# Sheet3.net
KiCad netlist of a schematic drawn in Altium Designer
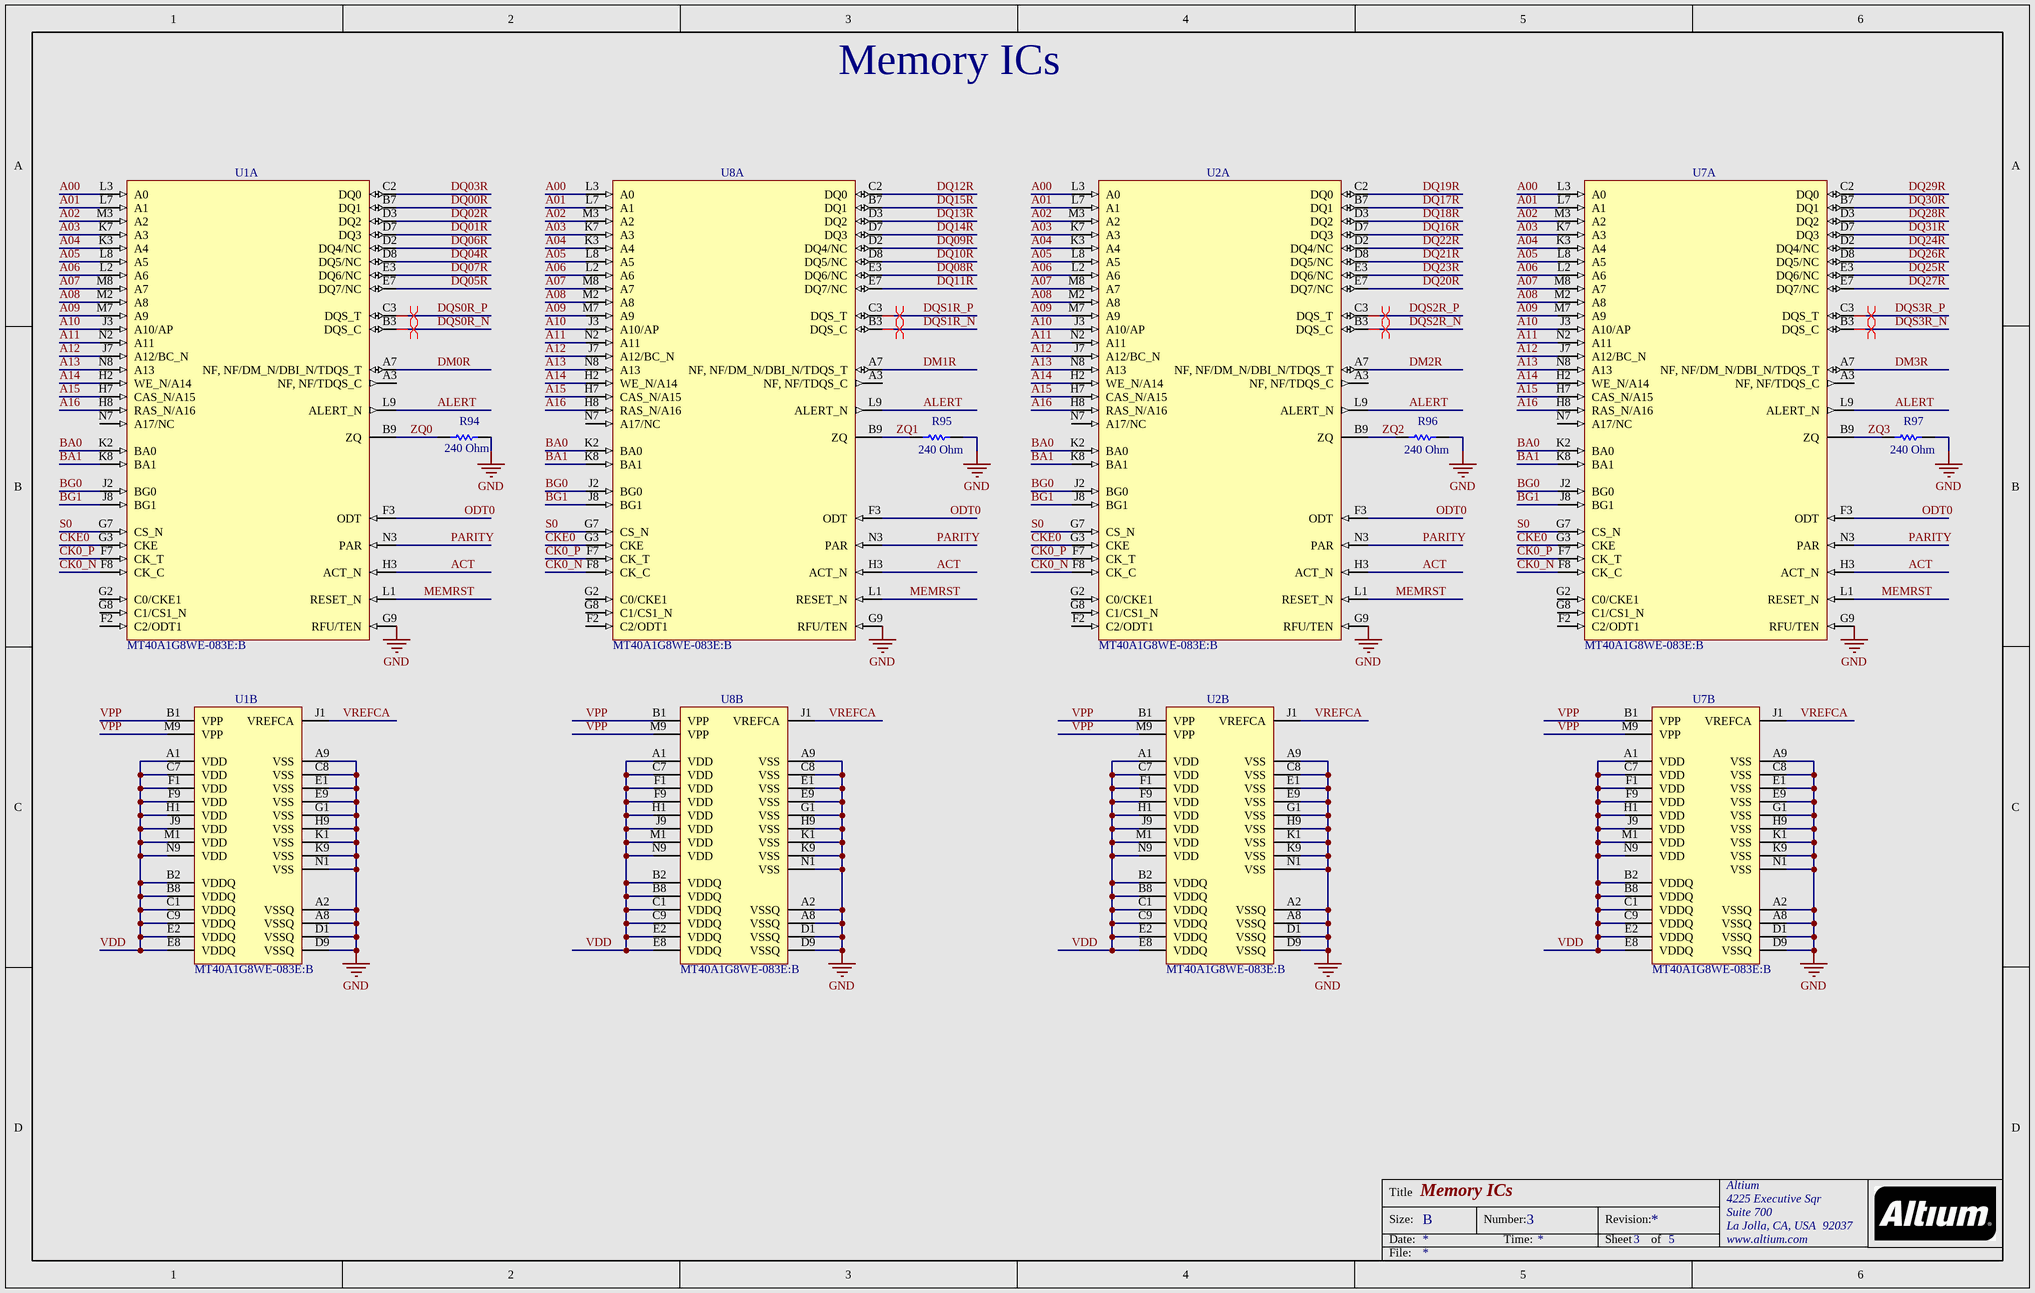
[diagram p0: Sheet3.SchDoc]

(export (version "E")
  (design (tool "Eeschema 10.0.6"))
  (components
    (comp (ref "R94")
      (value "ERJ-2GEJ241x")
      (footprint "RESC1005X40X25ML05T05")
      (description "Chip Resistor, 240 Ohm, +/- 5%, 100 mW, -55 to 155 degC, 0402 (1005 Metric), RoHS, Tape and Reel")
      (fields
        (field (name "RESISTANCE") "240 Ohm")
        (field (name "TOLERANCE") "5%")
        (field (name "MANUFACTURER") "Basic Passives")
      )
      (libsource (lib "Altium Content Vault") (part "CMP-2002-00493-3"))
    )
    (comp (ref "R95")
      (value "ERJ-2GEJ241x")
      (footprint "RESC1005X40X25ML05T05")
      (description "Chip Resistor, 240 Ohm, +/- 5%, 100 mW, -55 to 155 degC, 0402 (1005 Metric), RoHS, Tape and Reel")
      (fields
        (field (name "RESISTANCE") "240 Ohm")
        (field (name "TOLERANCE") "5%")
        (field (name "MANUFACTURER") "Basic Passives")
      )
      (libsource (lib "Altium Content Vault") (part "CMP-2002-00493-3"))
    )
    (comp (ref "R96")
      (value "ERJ-2GEJ241x")
      (footprint "RESC1005X40X25ML05T05")
      (description "Chip Resistor, 240 Ohm, +/- 5%, 100 mW, -55 to 155 degC, 0402 (1005 Metric), RoHS, Tape and Reel")
      (fields
        (field (name "RESISTANCE") "240 Ohm")
        (field (name "TOLERANCE") "5%")
        (field (name "MANUFACTURER") "Basic Passives")
      )
      (libsource (lib "Altium Content Vault") (part "CMP-2002-00493-3"))
    )
    (comp (ref "R97")
      (value "ERJ-2GEJ241x")
      (footprint "RESC1005X40X25ML05T05")
      (description "Chip Resistor, 240 Ohm, +/- 5%, 100 mW, -55 to 155 degC, 0402 (1005 Metric), RoHS, Tape and Reel")
      (fields
        (field (name "RESISTANCE") "240 Ohm")
        (field (name "TOLERANCE") "5%")
        (field (name "MANUFACTURER") "Basic Passives")
      )
      (libsource (lib "Altium Content Vault") (part "CMP-2002-00493-3"))
    )
    (comp (ref "U1")
      (value "MT40A1G8WE-083E:B")
      (footprint "MICT-WE-78")
      (description "8 Gb DDR4 SDRAM, 1 Gig x 8, 1.2 V, 0 to 95 degC, 78-Ball FBGA (WE), RoHS")
      (libsource (lib "Altium Content Vault") (part "CMP-1738-00001-1"))
    )
    (comp (ref "U2")
      (value "MT40A1G8WE-083E:B")
      (footprint "MICT-WE-78")
      (description "8 Gb DDR4 SDRAM, 1 Gig x 8, 1.2 V, 0 to 95 degC, 78-Ball FBGA (WE), RoHS")
      (libsource (lib "Altium Content Vault") (part "CMP-1738-00001-1"))
    )
    (comp (ref "U7")
      (value "MT40A1G8WE-083E:B")
      (footprint "MICT-WE-78")
      (description "8 Gb DDR4 SDRAM, 1 Gig x 8, 1.2 V, 0 to 95 degC, 78-Ball FBGA (WE), RoHS")
      (libsource (lib "Altium Content Vault") (part "CMP-1738-00001-1"))
    )
    (comp (ref "U8")
      (value "MT40A1G8WE-083E:B")
      (footprint "MICT-WE-78")
      (description "8 Gb DDR4 SDRAM, 1 Gig x 8, 1.2 V, 0 to 95 degC, 78-Ball FBGA (WE), RoHS")
      (libsource (lib "Altium Content Vault") (part "CMP-1738-00001-1"))
    )
  )
  (nets
    (net (code "1") (name "/A00") (class "Default")
      (node (ref "U1") (pin "L3") (pinfunction "A0_L3") (pintype "input"))
      (node (ref "U2") (pin "L3") (pinfunction "A0_L3") (pintype "input"))
      (node (ref "U7") (pin "L3") (pinfunction "A0_L3") (pintype "input"))
      (node (ref "U8") (pin "L3") (pinfunction "A0_L3") (pintype "input"))
    )
    (net (code "2") (name "/A01") (class "Default")
      (node (ref "U1") (pin "L7") (pinfunction "A1_L7") (pintype "input"))
      (node (ref "U2") (pin "L7") (pinfunction "A1_L7") (pintype "input"))
      (node (ref "U7") (pin "L7") (pinfunction "A1_L7") (pintype "input"))
      (node (ref "U8") (pin "L7") (pinfunction "A1_L7") (pintype "input"))
    )
    (net (code "3") (name "/A02") (class "Default")
      (node (ref "U1") (pin "M3") (pinfunction "A2_M3") (pintype "input"))
      (node (ref "U2") (pin "M3") (pinfunction "A2_M3") (pintype "input"))
      (node (ref "U7") (pin "M3") (pinfunction "A2_M3") (pintype "input"))
      (node (ref "U8") (pin "M3") (pinfunction "A2_M3") (pintype "input"))
    )
    (net (code "4") (name "/A03") (class "Default")
      (node (ref "U1") (pin "K7") (pinfunction "A3_K7") (pintype "input"))
      (node (ref "U2") (pin "K7") (pinfunction "A3_K7") (pintype "input"))
      (node (ref "U7") (pin "K7") (pinfunction "A3_K7") (pintype "input"))
      (node (ref "U8") (pin "K7") (pinfunction "A3_K7") (pintype "input"))
    )
    (net (code "5") (name "/A04") (class "Default")
      (node (ref "U1") (pin "K3") (pinfunction "A4_K3") (pintype "input"))
      (node (ref "U2") (pin "K3") (pinfunction "A4_K3") (pintype "input"))
      (node (ref "U7") (pin "K3") (pinfunction "A4_K3") (pintype "input"))
      (node (ref "U8") (pin "K3") (pinfunction "A4_K3") (pintype "input"))
    )
    (net (code "6") (name "/A05") (class "Default")
      (node (ref "U1") (pin "L8") (pinfunction "A5_L8") (pintype "input"))
      (node (ref "U2") (pin "L8") (pinfunction "A5_L8") (pintype "input"))
      (node (ref "U7") (pin "L8") (pinfunction "A5_L8") (pintype "input"))
      (node (ref "U8") (pin "L8") (pinfunction "A5_L8") (pintype "input"))
    )
    (net (code "7") (name "/A06") (class "Default")
      (node (ref "U1") (pin "L2") (pinfunction "A6_L2") (pintype "input"))
      (node (ref "U2") (pin "L2") (pinfunction "A6_L2") (pintype "input"))
      (node (ref "U7") (pin "L2") (pinfunction "A6_L2") (pintype "input"))
      (node (ref "U8") (pin "L2") (pinfunction "A6_L2") (pintype "input"))
    )
    (net (code "8") (name "/A07") (class "Default")
      (node (ref "U1") (pin "M8") (pinfunction "A7_M8") (pintype "input"))
      (node (ref "U2") (pin "M8") (pinfunction "A7_M8") (pintype "input"))
      (node (ref "U7") (pin "M8") (pinfunction "A7_M8") (pintype "input"))
      (node (ref "U8") (pin "M8") (pinfunction "A7_M8") (pintype "input"))
    )
    (net (code "9") (name "/A08") (class "Default")
      (node (ref "U1") (pin "M2") (pinfunction "A8_M2") (pintype "input"))
      (node (ref "U2") (pin "M2") (pinfunction "A8_M2") (pintype "input"))
      (node (ref "U7") (pin "M2") (pinfunction "A8_M2") (pintype "input"))
      (node (ref "U8") (pin "M2") (pinfunction "A8_M2") (pintype "input"))
    )
    (net (code "10") (name "/A09") (class "Default")
      (node (ref "U1") (pin "M7") (pinfunction "A9_M7") (pintype "input"))
      (node (ref "U2") (pin "M7") (pinfunction "A9_M7") (pintype "input"))
      (node (ref "U7") (pin "M7") (pinfunction "A9_M7") (pintype "input"))
      (node (ref "U8") (pin "M7") (pinfunction "A9_M7") (pintype "input"))
    )
    (net (code "11") (name "/A10") (class "Default")
      (node (ref "U1") (pin "J3") (pinfunction "A10/AP_J3") (pintype "input"))
      (node (ref "U2") (pin "J3") (pinfunction "A10/AP_J3") (pintype "input"))
      (node (ref "U7") (pin "J3") (pinfunction "A10/AP_J3") (pintype "input"))
      (node (ref "U8") (pin "J3") (pinfunction "A10/AP_J3") (pintype "input"))
    )
    (net (code "12") (name "/A11") (class "Default")
      (node (ref "U1") (pin "N2") (pinfunction "A11_N2") (pintype "input"))
      (node (ref "U2") (pin "N2") (pinfunction "A11_N2") (pintype "input"))
      (node (ref "U7") (pin "N2") (pinfunction "A11_N2") (pintype "input"))
      (node (ref "U8") (pin "N2") (pinfunction "A11_N2") (pintype "input"))
    )
    (net (code "13") (name "/A12") (class "Default")
      (node (ref "U1") (pin "J7") (pinfunction "A12/BC_N_J7") (pintype "input"))
      (node (ref "U2") (pin "J7") (pinfunction "A12/BC_N_J7") (pintype "input"))
      (node (ref "U7") (pin "J7") (pinfunction "A12/BC_N_J7") (pintype "input"))
      (node (ref "U8") (pin "J7") (pinfunction "A12/BC_N_J7") (pintype "input"))
    )
    (net (code "14") (name "/A13") (class "Default")
      (node (ref "U1") (pin "N8") (pinfunction "A13_N8") (pintype "input"))
      (node (ref "U2") (pin "N8") (pinfunction "A13_N8") (pintype "input"))
      (node (ref "U7") (pin "N8") (pinfunction "A13_N8") (pintype "input"))
      (node (ref "U8") (pin "N8") (pinfunction "A13_N8") (pintype "input"))
    )
    (net (code "15") (name "/A14") (class "Default")
      (node (ref "U1") (pin "H2") (pinfunction "WE_N/A14_H2") (pintype "input"))
      (node (ref "U2") (pin "H2") (pinfunction "WE_N/A14_H2") (pintype "input"))
      (node (ref "U7") (pin "H2") (pinfunction "WE_N/A14_H2") (pintype "input"))
      (node (ref "U8") (pin "H2") (pinfunction "WE_N/A14_H2") (pintype "input"))
    )
    (net (code "16") (name "/A15") (class "Default")
      (node (ref "U1") (pin "H7") (pinfunction "CAS_N/A15_H7") (pintype "input"))
      (node (ref "U2") (pin "H7") (pinfunction "CAS_N/A15_H7") (pintype "input"))
      (node (ref "U7") (pin "H7") (pinfunction "CAS_N/A15_H7") (pintype "input"))
      (node (ref "U8") (pin "H7") (pinfunction "CAS_N/A15_H7") (pintype "input"))
    )
    (net (code "17") (name "/A16") (class "Default")
      (node (ref "U1") (pin "H8") (pinfunction "RAS_N/A16_H8") (pintype "input"))
      (node (ref "U2") (pin "H8") (pinfunction "RAS_N/A16_H8") (pintype "input"))
      (node (ref "U7") (pin "H8") (pinfunction "RAS_N/A16_H8") (pintype "input"))
      (node (ref "U8") (pin "H8") (pinfunction "RAS_N/A16_H8") (pintype "input"))
    )
    (net (code "18") (name "/ACT") (class "Default")
      (node (ref "U1") (pin "H3") (pinfunction "ACT_N_H3") (pintype "input"))
      (node (ref "U2") (pin "H3") (pinfunction "ACT_N_H3") (pintype "input"))
      (node (ref "U7") (pin "H3") (pinfunction "ACT_N_H3") (pintype "input"))
      (node (ref "U8") (pin "H3") (pinfunction "ACT_N_H3") (pintype "input"))
    )
    (net (code "19") (name "/ALERT") (class "Default")
      (node (ref "U1") (pin "L9") (pinfunction "ALERT_N_L9") (pintype "output"))
      (node (ref "U2") (pin "L9") (pinfunction "ALERT_N_L9") (pintype "output"))
      (node (ref "U7") (pin "L9") (pinfunction "ALERT_N_L9") (pintype "output"))
      (node (ref "U8") (pin "L9") (pinfunction "ALERT_N_L9") (pintype "output"))
    )
    (net (code "20") (name "/BA0") (class "Default")
      (node (ref "U1") (pin "K2") (pinfunction "BA0_K2") (pintype "input"))
      (node (ref "U2") (pin "K2") (pinfunction "BA0_K2") (pintype "input"))
      (node (ref "U7") (pin "K2") (pinfunction "BA0_K2") (pintype "input"))
      (node (ref "U8") (pin "K2") (pinfunction "BA0_K2") (pintype "input"))
    )
    (net (code "21") (name "/BA1") (class "Default")
      (node (ref "U1") (pin "K8") (pinfunction "BA1_K8") (pintype "input"))
      (node (ref "U2") (pin "K8") (pinfunction "BA1_K8") (pintype "input"))
      (node (ref "U7") (pin "K8") (pinfunction "BA1_K8") (pintype "input"))
      (node (ref "U8") (pin "K8") (pinfunction "BA1_K8") (pintype "input"))
    )
    (net (code "22") (name "/BG0") (class "Default")
      (node (ref "U1") (pin "J2") (pinfunction "BG0_J2") (pintype "input"))
      (node (ref "U2") (pin "J2") (pinfunction "BG0_J2") (pintype "input"))
      (node (ref "U7") (pin "J2") (pinfunction "BG0_J2") (pintype "input"))
      (node (ref "U8") (pin "J2") (pinfunction "BG0_J2") (pintype "input"))
    )
    (net (code "23") (name "/BG1") (class "Default")
      (node (ref "U1") (pin "J8") (pinfunction "BG1_J8") (pintype "input"))
      (node (ref "U2") (pin "J8") (pinfunction "BG1_J8") (pintype "input"))
      (node (ref "U7") (pin "J8") (pinfunction "BG1_J8") (pintype "input"))
      (node (ref "U8") (pin "J8") (pinfunction "BG1_J8") (pintype "input"))
    )
    (net (code "24") (name "/CK0_N") (class "Default")
      (node (ref "U1") (pin "F8") (pinfunction "CK_C_F8") (pintype "input"))
      (node (ref "U2") (pin "F8") (pinfunction "CK_C_F8") (pintype "input"))
      (node (ref "U7") (pin "F8") (pinfunction "CK_C_F8") (pintype "input"))
      (node (ref "U8") (pin "F8") (pinfunction "CK_C_F8") (pintype "input"))
    )
    (net (code "25") (name "/CK0_P") (class "Default")
      (node (ref "U1") (pin "F7") (pinfunction "CK_T_F7") (pintype "input"))
      (node (ref "U2") (pin "F7") (pinfunction "CK_T_F7") (pintype "input"))
      (node (ref "U7") (pin "F7") (pinfunction "CK_T_F7") (pintype "input"))
      (node (ref "U8") (pin "F7") (pinfunction "CK_T_F7") (pintype "input"))
    )
    (net (code "26") (name "/CKE0") (class "Default")
      (node (ref "U1") (pin "G3") (pinfunction "CKE_G3") (pintype "input"))
      (node (ref "U2") (pin "G3") (pinfunction "CKE_G3") (pintype "input"))
      (node (ref "U7") (pin "G3") (pinfunction "CKE_G3") (pintype "input"))
      (node (ref "U8") (pin "G3") (pinfunction "CKE_G3") (pintype "input"))
    )
    (net (code "27") (name "/DM0R") (class "Default")
      (node (ref "U1") (pin "A7") (pinfunction "NF,_NF/DM_N/DBI_N/TDQS_T_A7") (pintype "bidirectional"))
    )
    (net (code "28") (name "/DM1R") (class "Default")
      (node (ref "U8") (pin "A7") (pinfunction "NF,_NF/DM_N/DBI_N/TDQS_T_A7") (pintype "bidirectional"))
    )
    (net (code "29") (name "/DM2R") (class "Default")
      (node (ref "U2") (pin "A7") (pinfunction "NF,_NF/DM_N/DBI_N/TDQS_T_A7") (pintype "bidirectional"))
    )
    (net (code "30") (name "/DM3R") (class "Default")
      (node (ref "U7") (pin "A7") (pinfunction "NF,_NF/DM_N/DBI_N/TDQS_T_A7") (pintype "bidirectional"))
    )
    (net (code "31") (name "/DQ00R") (class "Default")
      (node (ref "U1") (pin "B7") (pinfunction "DQ1_B7") (pintype "bidirectional"))
    )
    (net (code "32") (name "/DQ01R") (class "Default")
      (node (ref "U1") (pin "D7") (pinfunction "DQ3_D7") (pintype "bidirectional"))
    )
    (net (code "33") (name "/DQ02R") (class "Default")
      (node (ref "U1") (pin "D3") (pinfunction "DQ2_D3") (pintype "bidirectional"))
    )
    (net (code "34") (name "/DQ03R") (class "Default")
      (node (ref "U1") (pin "C2") (pinfunction "DQ0_C2") (pintype "bidirectional"))
    )
    (net (code "35") (name "/DQ04R") (class "Default")
      (node (ref "U1") (pin "D8") (pinfunction "DQ5/NC_D8") (pintype "bidirectional"))
    )
    (net (code "36") (name "/DQ05R") (class "Default")
      (node (ref "U1") (pin "E7") (pinfunction "DQ7/NC_E7") (pintype "bidirectional"))
    )
    (net (code "37") (name "/DQ06R") (class "Default")
      (node (ref "U1") (pin "D2") (pinfunction "DQ4/NC_D2") (pintype "bidirectional"))
    )
    (net (code "38") (name "/DQ07R") (class "Default")
      (node (ref "U1") (pin "E3") (pinfunction "DQ6/NC_E3") (pintype "bidirectional"))
    )
    (net (code "39") (name "/DQ08R") (class "Default")
      (node (ref "U8") (pin "E3") (pinfunction "DQ6/NC_E3") (pintype "bidirectional"))
    )
    (net (code "40") (name "/DQ09R") (class "Default")
      (node (ref "U8") (pin "D2") (pinfunction "DQ4/NC_D2") (pintype "bidirectional"))
    )
    (net (code "41") (name "/DQ10R") (class "Default")
      (node (ref "U8") (pin "D8") (pinfunction "DQ5/NC_D8") (pintype "bidirectional"))
    )
    (net (code "42") (name "/DQ11R") (class "Default")
      (node (ref "U8") (pin "E7") (pinfunction "DQ7/NC_E7") (pintype "bidirectional"))
    )
    (net (code "43") (name "/DQ12R") (class "Default")
      (node (ref "U8") (pin "C2") (pinfunction "DQ0_C2") (pintype "bidirectional"))
    )
    (net (code "44") (name "/DQ13R") (class "Default")
      (node (ref "U8") (pin "D3") (pinfunction "DQ2_D3") (pintype "bidirectional"))
    )
    (net (code "45") (name "/DQ14R") (class "Default")
      (node (ref "U8") (pin "D7") (pinfunction "DQ3_D7") (pintype "bidirectional"))
    )
    (net (code "46") (name "/DQ15R") (class "Default")
      (node (ref "U8") (pin "B7") (pinfunction "DQ1_B7") (pintype "bidirectional"))
    )
    (net (code "47") (name "/DQ16R") (class "Default")
      (node (ref "U2") (pin "D7") (pinfunction "DQ3_D7") (pintype "bidirectional"))
    )
    (net (code "48") (name "/DQ17R") (class "Default")
      (node (ref "U2") (pin "B7") (pinfunction "DQ1_B7") (pintype "bidirectional"))
    )
    (net (code "49") (name "/DQ18R") (class "Default")
      (node (ref "U2") (pin "D3") (pinfunction "DQ2_D3") (pintype "bidirectional"))
    )
    (net (code "50") (name "/DQ19R") (class "Default")
      (node (ref "U2") (pin "C2") (pinfunction "DQ0_C2") (pintype "bidirectional"))
    )
    (net (code "51") (name "/DQ20R") (class "Default")
      (node (ref "U2") (pin "E7") (pinfunction "DQ7/NC_E7") (pintype "bidirectional"))
    )
    (net (code "52") (name "/DQ21R") (class "Default")
      (node (ref "U2") (pin "D8") (pinfunction "DQ5/NC_D8") (pintype "bidirectional"))
    )
    (net (code "53") (name "/DQ22R") (class "Default")
      (node (ref "U2") (pin "D2") (pinfunction "DQ4/NC_D2") (pintype "bidirectional"))
    )
    (net (code "54") (name "/DQ23R") (class "Default")
      (node (ref "U2") (pin "E3") (pinfunction "DQ6/NC_E3") (pintype "bidirectional"))
    )
    (net (code "55") (name "/DQ24R") (class "Default")
      (node (ref "U7") (pin "D2") (pinfunction "DQ4/NC_D2") (pintype "bidirectional"))
    )
    (net (code "56") (name "/DQ25R") (class "Default")
      (node (ref "U7") (pin "E3") (pinfunction "DQ6/NC_E3") (pintype "bidirectional"))
    )
    (net (code "57") (name "/DQ26R") (class "Default")
      (node (ref "U7") (pin "D8") (pinfunction "DQ5/NC_D8") (pintype "bidirectional"))
    )
    (net (code "58") (name "/DQ27R") (class "Default")
      (node (ref "U7") (pin "E7") (pinfunction "DQ7/NC_E7") (pintype "bidirectional"))
    )
    (net (code "59") (name "/DQ28R") (class "Default")
      (node (ref "U7") (pin "D3") (pinfunction "DQ2_D3") (pintype "bidirectional"))
    )
    (net (code "60") (name "/DQ29R") (class "Default")
      (node (ref "U7") (pin "C2") (pinfunction "DQ0_C2") (pintype "bidirectional"))
    )
    (net (code "61") (name "/DQ30R") (class "Default")
      (node (ref "U7") (pin "B7") (pinfunction "DQ1_B7") (pintype "bidirectional"))
    )
    (net (code "62") (name "/DQ31R") (class "Default")
      (node (ref "U7") (pin "D7") (pinfunction "DQ3_D7") (pintype "bidirectional"))
    )
    (net (code "63") (name "/DQS0R_N") (class "Default")
      (node (ref "U1") (pin "B3") (pinfunction "DQS_C_B3") (pintype "bidirectional"))
    )
    (net (code "64") (name "/DQS0R_P") (class "Default")
      (node (ref "U1") (pin "C3") (pinfunction "DQS_T_C3") (pintype "bidirectional"))
    )
    (net (code "65") (name "/DQS1R_N") (class "Default")
      (node (ref "U8") (pin "B3") (pinfunction "DQS_C_B3") (pintype "bidirectional"))
    )
    (net (code "66") (name "/DQS1R_P") (class "Default")
      (node (ref "U8") (pin "C3") (pinfunction "DQS_T_C3") (pintype "bidirectional"))
    )
    (net (code "67") (name "/DQS2R_N") (class "Default")
      (node (ref "U2") (pin "B3") (pinfunction "DQS_C_B3") (pintype "bidirectional"))
    )
    (net (code "68") (name "/DQS2R_P") (class "Default")
      (node (ref "U2") (pin "C3") (pinfunction "DQS_T_C3") (pintype "bidirectional"))
    )
    (net (code "69") (name "/DQS3R_N") (class "Default")
      (node (ref "U7") (pin "B3") (pinfunction "DQS_C_B3") (pintype "bidirectional"))
    )
    (net (code "70") (name "/DQS3R_P") (class "Default")
      (node (ref "U7") (pin "C3") (pinfunction "DQS_T_C3") (pintype "bidirectional"))
    )
    (net (code "71") (name "/MEMRST") (class "Default")
      (node (ref "U1") (pin "L1") (pinfunction "RESET_N_L1") (pintype "input"))
      (node (ref "U2") (pin "L1") (pinfunction "RESET_N_L1") (pintype "input"))
      (node (ref "U7") (pin "L1") (pinfunction "RESET_N_L1") (pintype "input"))
      (node (ref "U8") (pin "L1") (pinfunction "RESET_N_L1") (pintype "input"))
    )
    (net (code "72") (name "/ODT0") (class "Default")
      (node (ref "U1") (pin "F3") (pinfunction "ODT_F3") (pintype "input"))
      (node (ref "U2") (pin "F3") (pinfunction "ODT_F3") (pintype "input"))
      (node (ref "U7") (pin "F3") (pinfunction "ODT_F3") (pintype "input"))
      (node (ref "U8") (pin "F3") (pinfunction "ODT_F3") (pintype "input"))
    )
    (net (code "73") (name "/PARITY") (class "Default")
      (node (ref "U1") (pin "N3") (pinfunction "PAR_N3") (pintype "input"))
      (node (ref "U2") (pin "N3") (pinfunction "PAR_N3") (pintype "input"))
      (node (ref "U7") (pin "N3") (pinfunction "PAR_N3") (pintype "input"))
      (node (ref "U8") (pin "N3") (pinfunction "PAR_N3") (pintype "input"))
    )
    (net (code "74") (name "/S0") (class "Default")
      (node (ref "U1") (pin "G7") (pinfunction "CS_N_G7") (pintype "input"))
      (node (ref "U2") (pin "G7") (pinfunction "CS_N_G7") (pintype "input"))
      (node (ref "U7") (pin "G7") (pinfunction "CS_N_G7") (pintype "input"))
      (node (ref "U8") (pin "G7") (pinfunction "CS_N_G7") (pintype "input"))
    )
    (net (code "75") (name "/VDD") (class "Default")
      (node (ref "U1") (pin "A1") (pinfunction "VDD_A1") (pintype "power_in"))
      (node (ref "U1") (pin "B2") (pinfunction "VDDQ_B2") (pintype "power_in"))
      (node (ref "U1") (pin "B8") (pinfunction "VDDQ_B8") (pintype "power_in"))
      (node (ref "U1") (pin "C1") (pinfunction "VDDQ_C1") (pintype "power_in"))
      (node (ref "U1") (pin "C7") (pinfunction "VDD_C7") (pintype "power_in"))
      (node (ref "U1") (pin "C9") (pinfunction "VDDQ_C9") (pintype "power_in"))
      (node (ref "U1") (pin "E2") (pinfunction "VDDQ_E2") (pintype "power_in"))
      (node (ref "U1") (pin "E8") (pinfunction "VDDQ_E8") (pintype "power_in"))
      (node (ref "U1") (pin "F1") (pinfunction "VDD_F1") (pintype "power_in"))
      (node (ref "U1") (pin "F9") (pinfunction "VDD_F9") (pintype "power_in"))
      (node (ref "U1") (pin "H1") (pinfunction "VDD_H1") (pintype "power_in"))
      (node (ref "U1") (pin "J9") (pinfunction "VDD_J9") (pintype "power_in"))
      (node (ref "U1") (pin "M1") (pinfunction "VDD_M1") (pintype "power_in"))
      (node (ref "U1") (pin "N9") (pinfunction "VDD_N9") (pintype "power_in"))
      (node (ref "U2") (pin "A1") (pinfunction "VDD_A1") (pintype "power_in"))
      (node (ref "U2") (pin "B2") (pinfunction "VDDQ_B2") (pintype "power_in"))
      (node (ref "U2") (pin "B8") (pinfunction "VDDQ_B8") (pintype "power_in"))
      (node (ref "U2") (pin "C1") (pinfunction "VDDQ_C1") (pintype "power_in"))
      (node (ref "U2") (pin "C7") (pinfunction "VDD_C7") (pintype "power_in"))
      (node (ref "U2") (pin "C9") (pinfunction "VDDQ_C9") (pintype "power_in"))
      (node (ref "U2") (pin "E2") (pinfunction "VDDQ_E2") (pintype "power_in"))
      (node (ref "U2") (pin "E8") (pinfunction "VDDQ_E8") (pintype "power_in"))
      (node (ref "U2") (pin "F1") (pinfunction "VDD_F1") (pintype "power_in"))
      (node (ref "U2") (pin "F9") (pinfunction "VDD_F9") (pintype "power_in"))
      (node (ref "U2") (pin "H1") (pinfunction "VDD_H1") (pintype "power_in"))
      (node (ref "U2") (pin "J9") (pinfunction "VDD_J9") (pintype "power_in"))
      (node (ref "U2") (pin "M1") (pinfunction "VDD_M1") (pintype "power_in"))
      (node (ref "U2") (pin "N9") (pinfunction "VDD_N9") (pintype "power_in"))
      (node (ref "U7") (pin "A1") (pinfunction "VDD_A1") (pintype "power_in"))
      (node (ref "U7") (pin "B2") (pinfunction "VDDQ_B2") (pintype "power_in"))
      (node (ref "U7") (pin "B8") (pinfunction "VDDQ_B8") (pintype "power_in"))
      (node (ref "U7") (pin "C1") (pinfunction "VDDQ_C1") (pintype "power_in"))
      (node (ref "U7") (pin "C7") (pinfunction "VDD_C7") (pintype "power_in"))
      (node (ref "U7") (pin "C9") (pinfunction "VDDQ_C9") (pintype "power_in"))
      (node (ref "U7") (pin "E2") (pinfunction "VDDQ_E2") (pintype "power_in"))
      (node (ref "U7") (pin "E8") (pinfunction "VDDQ_E8") (pintype "power_in"))
      (node (ref "U7") (pin "F1") (pinfunction "VDD_F1") (pintype "power_in"))
      (node (ref "U7") (pin "F9") (pinfunction "VDD_F9") (pintype "power_in"))
      (node (ref "U7") (pin "H1") (pinfunction "VDD_H1") (pintype "power_in"))
      (node (ref "U7") (pin "J9") (pinfunction "VDD_J9") (pintype "power_in"))
      (node (ref "U7") (pin "M1") (pinfunction "VDD_M1") (pintype "power_in"))
      (node (ref "U7") (pin "N9") (pinfunction "VDD_N9") (pintype "power_in"))
      (node (ref "U8") (pin "A1") (pinfunction "VDD_A1") (pintype "power_in"))
      (node (ref "U8") (pin "B2") (pinfunction "VDDQ_B2") (pintype "power_in"))
      (node (ref "U8") (pin "B8") (pinfunction "VDDQ_B8") (pintype "power_in"))
      (node (ref "U8") (pin "C1") (pinfunction "VDDQ_C1") (pintype "power_in"))
      (node (ref "U8") (pin "C7") (pinfunction "VDD_C7") (pintype "power_in"))
      (node (ref "U8") (pin "C9") (pinfunction "VDDQ_C9") (pintype "power_in"))
      (node (ref "U8") (pin "E2") (pinfunction "VDDQ_E2") (pintype "power_in"))
      (node (ref "U8") (pin "E8") (pinfunction "VDDQ_E8") (pintype "power_in"))
      (node (ref "U8") (pin "F1") (pinfunction "VDD_F1") (pintype "power_in"))
      (node (ref "U8") (pin "F9") (pinfunction "VDD_F9") (pintype "power_in"))
      (node (ref "U8") (pin "H1") (pinfunction "VDD_H1") (pintype "power_in"))
      (node (ref "U8") (pin "J9") (pinfunction "VDD_J9") (pintype "power_in"))
      (node (ref "U8") (pin "M1") (pinfunction "VDD_M1") (pintype "power_in"))
      (node (ref "U8") (pin "N9") (pinfunction "VDD_N9") (pintype "power_in"))
    )
    (net (code "76") (name "/VPP") (class "Default")
      (node (ref "U1") (pin "B1") (pinfunction "VPP_B1") (pintype "power_in"))
      (node (ref "U1") (pin "M9") (pinfunction "VPP_M9") (pintype "power_in"))
      (node (ref "U2") (pin "B1") (pinfunction "VPP_B1") (pintype "power_in"))
      (node (ref "U2") (pin "M9") (pinfunction "VPP_M9") (pintype "power_in"))
      (node (ref "U7") (pin "B1") (pinfunction "VPP_B1") (pintype "power_in"))
      (node (ref "U7") (pin "M9") (pinfunction "VPP_M9") (pintype "power_in"))
      (node (ref "U8") (pin "B1") (pinfunction "VPP_B1") (pintype "power_in"))
      (node (ref "U8") (pin "M9") (pinfunction "VPP_M9") (pintype "power_in"))
    )
    (net (code "77") (name "/VREFCA") (class "Default")
      (node (ref "U1") (pin "J1") (pinfunction "VREFCA_J1") (pintype "passive"))
      (node (ref "U2") (pin "J1") (pinfunction "VREFCA_J1") (pintype "passive"))
      (node (ref "U7") (pin "J1") (pinfunction "VREFCA_J1") (pintype "passive"))
      (node (ref "U8") (pin "J1") (pinfunction "VREFCA_J1") (pintype "passive"))
    )
    (net (code "78") (name "/ZQ0") (class "Default")
      (node (ref "R94") (pin "2") (pinfunction "2_2") (pintype "passive"))
      (node (ref "U1") (pin "B9") (pinfunction "ZQ_B9") (pintype "passive"))
    )
    (net (code "79") (name "/ZQ1") (class "Default")
      (node (ref "R95") (pin "2") (pinfunction "2_2") (pintype "passive"))
      (node (ref "U8") (pin "B9") (pinfunction "ZQ_B9") (pintype "passive"))
    )
    (net (code "80") (name "/ZQ2") (class "Default")
      (node (ref "R96") (pin "2") (pinfunction "2_2") (pintype "passive"))
      (node (ref "U2") (pin "B9") (pinfunction "ZQ_B9") (pintype "passive"))
    )
    (net (code "81") (name "/ZQ3") (class "Default")
      (node (ref "R97") (pin "2") (pinfunction "2_2") (pintype "passive"))
      (node (ref "U7") (pin "B9") (pinfunction "ZQ_B9") (pintype "passive"))
    )
    (net (code "82") (name "GND") (class "Default")
      (node (ref "R94") (pin "1") (pinfunction "1_1") (pintype "passive"))
      (node (ref "R95") (pin "1") (pinfunction "1_1") (pintype "passive"))
      (node (ref "R96") (pin "1") (pinfunction "1_1") (pintype "passive"))
      (node (ref "R97") (pin "1") (pinfunction "1_1") (pintype "passive"))
      (node (ref "U1") (pin "A2") (pinfunction "VSSQ_A2") (pintype "power_in"))
      (node (ref "U1") (pin "A8") (pinfunction "VSSQ_A8") (pintype "power_in"))
      (node (ref "U1") (pin "A9") (pinfunction "VSS_A9") (pintype "power_in"))
      (node (ref "U1") (pin "C8") (pinfunction "VSS_C8") (pintype "power_in"))
      (node (ref "U1") (pin "D1") (pinfunction "VSSQ_D1") (pintype "power_in"))
      (node (ref "U1") (pin "D9") (pinfunction "VSSQ_D9") (pintype "power_in"))
      (node (ref "U1") (pin "E1") (pinfunction "VSS_E1") (pintype "power_in"))
      (node (ref "U1") (pin "E9") (pinfunction "VSS_E9") (pintype "power_in"))
      (node (ref "U1") (pin "G1") (pinfunction "VSS_G1") (pintype "power_in"))
      (node (ref "U1") (pin "G9") (pinfunction "RFU/TEN_G9") (pintype "input"))
      (node (ref "U1") (pin "H9") (pinfunction "VSS_H9") (pintype "power_in"))
      (node (ref "U1") (pin "K1") (pinfunction "VSS_K1") (pintype "power_in"))
      (node (ref "U1") (pin "K9") (pinfunction "VSS_K9") (pintype "power_in"))
      (node (ref "U1") (pin "N1") (pinfunction "VSS_N1") (pintype "power_in"))
      (node (ref "U2") (pin "A2") (pinfunction "VSSQ_A2") (pintype "power_in"))
      (node (ref "U2") (pin "A8") (pinfunction "VSSQ_A8") (pintype "power_in"))
      (node (ref "U2") (pin "A9") (pinfunction "VSS_A9") (pintype "power_in"))
      (node (ref "U2") (pin "C8") (pinfunction "VSS_C8") (pintype "power_in"))
      (node (ref "U2") (pin "D1") (pinfunction "VSSQ_D1") (pintype "power_in"))
      (node (ref "U2") (pin "D9") (pinfunction "VSSQ_D9") (pintype "power_in"))
      (node (ref "U2") (pin "E1") (pinfunction "VSS_E1") (pintype "power_in"))
      (node (ref "U2") (pin "E9") (pinfunction "VSS_E9") (pintype "power_in"))
      (node (ref "U2") (pin "G1") (pinfunction "VSS_G1") (pintype "power_in"))
      (node (ref "U2") (pin "G9") (pinfunction "RFU/TEN_G9") (pintype "input"))
      (node (ref "U2") (pin "H9") (pinfunction "VSS_H9") (pintype "power_in"))
      (node (ref "U2") (pin "K1") (pinfunction "VSS_K1") (pintype "power_in"))
      (node (ref "U2") (pin "K9") (pinfunction "VSS_K9") (pintype "power_in"))
      (node (ref "U2") (pin "N1") (pinfunction "VSS_N1") (pintype "power_in"))
      (node (ref "U7") (pin "A2") (pinfunction "VSSQ_A2") (pintype "power_in"))
      (node (ref "U7") (pin "A8") (pinfunction "VSSQ_A8") (pintype "power_in"))
      (node (ref "U7") (pin "A9") (pinfunction "VSS_A9") (pintype "power_in"))
      (node (ref "U7") (pin "C8") (pinfunction "VSS_C8") (pintype "power_in"))
      (node (ref "U7") (pin "D1") (pinfunction "VSSQ_D1") (pintype "power_in"))
      (node (ref "U7") (pin "D9") (pinfunction "VSSQ_D9") (pintype "power_in"))
      (node (ref "U7") (pin "E1") (pinfunction "VSS_E1") (pintype "power_in"))
      (node (ref "U7") (pin "E9") (pinfunction "VSS_E9") (pintype "power_in"))
      (node (ref "U7") (pin "G1") (pinfunction "VSS_G1") (pintype "power_in"))
      (node (ref "U7") (pin "G9") (pinfunction "RFU/TEN_G9") (pintype "input"))
      (node (ref "U7") (pin "H9") (pinfunction "VSS_H9") (pintype "power_in"))
      (node (ref "U7") (pin "K1") (pinfunction "VSS_K1") (pintype "power_in"))
      (node (ref "U7") (pin "K9") (pinfunction "VSS_K9") (pintype "power_in"))
      (node (ref "U7") (pin "N1") (pinfunction "VSS_N1") (pintype "power_in"))
      (node (ref "U8") (pin "A2") (pinfunction "VSSQ_A2") (pintype "power_in"))
      (node (ref "U8") (pin "A8") (pinfunction "VSSQ_A8") (pintype "power_in"))
      (node (ref "U8") (pin "A9") (pinfunction "VSS_A9") (pintype "power_in"))
      (node (ref "U8") (pin "C8") (pinfunction "VSS_C8") (pintype "power_in"))
      (node (ref "U8") (pin "D1") (pinfunction "VSSQ_D1") (pintype "power_in"))
      (node (ref "U8") (pin "D9") (pinfunction "VSSQ_D9") (pintype "power_in"))
      (node (ref "U8") (pin "E1") (pinfunction "VSS_E1") (pintype "power_in"))
      (node (ref "U8") (pin "E9") (pinfunction "VSS_E9") (pintype "power_in"))
      (node (ref "U8") (pin "G1") (pinfunction "VSS_G1") (pintype "power_in"))
      (node (ref "U8") (pin "G9") (pinfunction "RFU/TEN_G9") (pintype "input"))
      (node (ref "U8") (pin "H9") (pinfunction "VSS_H9") (pintype "power_in"))
      (node (ref "U8") (pin "K1") (pinfunction "VSS_K1") (pintype "power_in"))
      (node (ref "U8") (pin "K9") (pinfunction "VSS_K9") (pintype "power_in"))
      (node (ref "U8") (pin "N1") (pinfunction "VSS_N1") (pintype "power_in"))
    )
    (net (code "83") (name "unconnected-(U1A-A17{slash}NC-PadN7)") (class "Default")
      (node (ref "U1") (pin "N7") (pinfunction "A17/NC_N7") (pintype "input"))
    )
    (net (code "84") (name "unconnected-(U1A-C0{slash}CKE1-PadG2)") (class "Default")
      (node (ref "U1") (pin "G2") (pinfunction "C0/CKE1_G2") (pintype "input"))
    )
    (net (code "85") (name "unconnected-(U1A-C1{slash}CS1_N-PadG8)") (class "Default")
      (node (ref "U1") (pin "G8") (pinfunction "C1/CS1_N_G8") (pintype "input"))
    )
    (net (code "86") (name "unconnected-(U1A-C2{slash}ODT1-PadF2)") (class "Default")
      (node (ref "U1") (pin "F2") (pinfunction "C2/ODT1_F2") (pintype "input"))
    )
    (net (code "87") (name "unconnected-(U1A-NF,_NF{slash}TDQS_C-PadA3)") (class "Default")
      (node (ref "U1") (pin "A3") (pinfunction "NF,_NF/TDQS_C_A3") (pintype "output"))
    )
    (net (code "88") (name "unconnected-(U2A-A17{slash}NC-PadN7)") (class "Default")
      (node (ref "U2") (pin "N7") (pinfunction "A17/NC_N7") (pintype "input"))
    )
    (net (code "89") (name "unconnected-(U2A-C0{slash}CKE1-PadG2)") (class "Default")
      (node (ref "U2") (pin "G2") (pinfunction "C0/CKE1_G2") (pintype "input"))
    )
    (net (code "90") (name "unconnected-(U2A-C1{slash}CS1_N-PadG8)") (class "Default")
      (node (ref "U2") (pin "G8") (pinfunction "C1/CS1_N_G8") (pintype "input"))
    )
    (net (code "91") (name "unconnected-(U2A-C2{slash}ODT1-PadF2)") (class "Default")
      (node (ref "U2") (pin "F2") (pinfunction "C2/ODT1_F2") (pintype "input"))
    )
    (net (code "92") (name "unconnected-(U2A-NF,_NF{slash}TDQS_C-PadA3)") (class "Default")
      (node (ref "U2") (pin "A3") (pinfunction "NF,_NF/TDQS_C_A3") (pintype "output"))
    )
    (net (code "93") (name "unconnected-(U7A-A17{slash}NC-PadN7)") (class "Default")
      (node (ref "U7") (pin "N7") (pinfunction "A17/NC_N7") (pintype "input"))
    )
    (net (code "94") (name "unconnected-(U7A-C0{slash}CKE1-PadG2)") (class "Default")
      (node (ref "U7") (pin "G2") (pinfunction "C0/CKE1_G2") (pintype "input"))
    )
    (net (code "95") (name "unconnected-(U7A-C1{slash}CS1_N-PadG8)") (class "Default")
      (node (ref "U7") (pin "G8") (pinfunction "C1/CS1_N_G8") (pintype "input"))
    )
    (net (code "96") (name "unconnected-(U7A-C2{slash}ODT1-PadF2)") (class "Default")
      (node (ref "U7") (pin "F2") (pinfunction "C2/ODT1_F2") (pintype "input"))
    )
    (net (code "97") (name "unconnected-(U7A-NF,_NF{slash}TDQS_C-PadA3)") (class "Default")
      (node (ref "U7") (pin "A3") (pinfunction "NF,_NF/TDQS_C_A3") (pintype "output"))
    )
    (net (code "98") (name "unconnected-(U8A-A17{slash}NC-PadN7)") (class "Default")
      (node (ref "U8") (pin "N7") (pinfunction "A17/NC_N7") (pintype "input"))
    )
    (net (code "99") (name "unconnected-(U8A-C0{slash}CKE1-PadG2)") (class "Default")
      (node (ref "U8") (pin "G2") (pinfunction "C0/CKE1_G2") (pintype "input"))
    )
    (net (code "100") (name "unconnected-(U8A-C1{slash}CS1_N-PadG8)") (class "Default")
      (node (ref "U8") (pin "G8") (pinfunction "C1/CS1_N_G8") (pintype "input"))
    )
    (net (code "101") (name "unconnected-(U8A-C2{slash}ODT1-PadF2)") (class "Default")
      (node (ref "U8") (pin "F2") (pinfunction "C2/ODT1_F2") (pintype "input"))
    )
    (net (code "102") (name "unconnected-(U8A-NF,_NF{slash}TDQS_C-PadA3)") (class "Default")
      (node (ref "U8") (pin "A3") (pinfunction "NF,_NF/TDQS_C_A3") (pintype "output"))
    )
  )
)
